# USB.net
KiCad netlist of a schematic drawn in Altium Designer
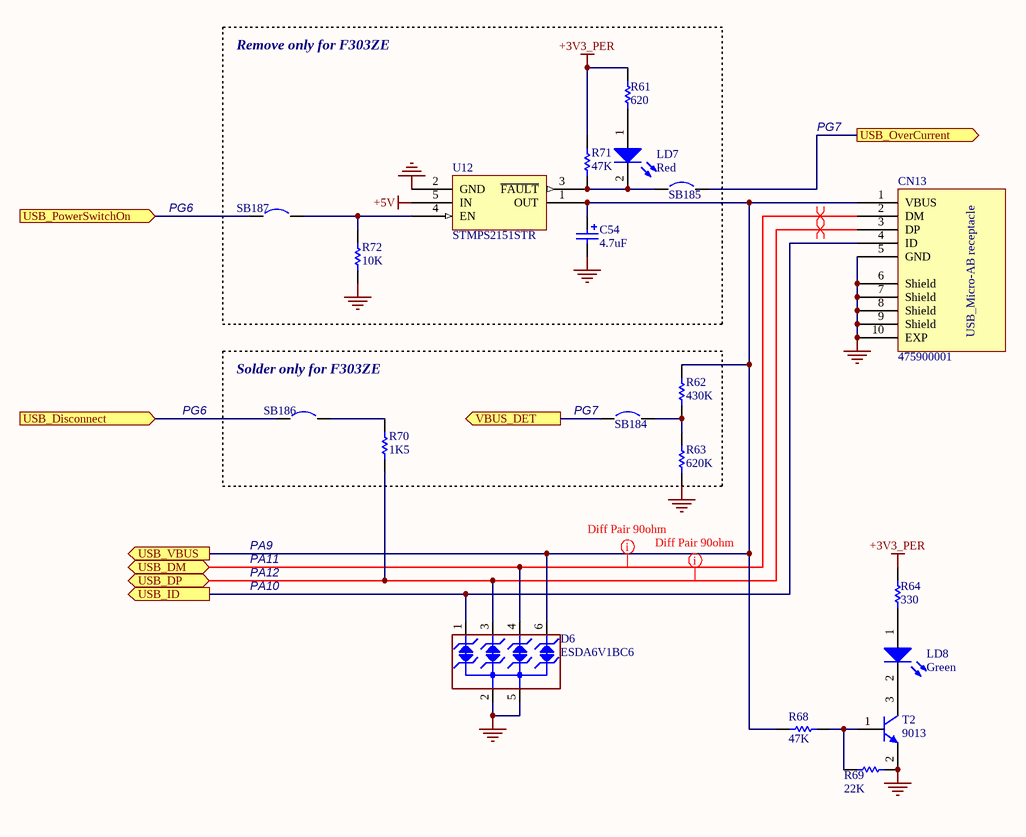
[diagram p0: USB.SchDoc]

(export (version "E")
  (design (tool "Eeschema 10.0.6"))
  (components
    (comp (ref "C54")
      (value "4.7uF")
      (footprint "TAN-A")
      (description "Polarized Capacitor (Radial)")
      (fields (field (name "PUBLISHER") "Altium Limited"))
      (libsource (lib "Miscellaneous Devices") (part "Cap Pol1"))
    )
    (comp (ref "CN13")
      (value "475900001")
      (footprint "MOLEX_47590001")
      (libsource (lib "mb1045") (part "475900001"))
    )
    (comp (ref "D6")
      (value "ESDA6V1BC6")
      (footprint "STM-SMEE:SOT23-6L")
      (description "4-line ESD protection")
      (libsource (lib "MB1137") (part "ESDA6V1BC6"))
    )
    (comp (ref "LD7")
      (value "Red")
      (footprint "0603D-R")
      (description "Typical RED, GREEN, YELLOW, AMBER GaAs LED")
      (fields (field (name "PUBLISHER") "Altium Limited"))
      (libsource (lib "Miscellaneous Devices") (part "LED2"))
    )
    (comp (ref "LD8")
      (value "Green")
      (footprint "0603D-G")
      (description "Typical RED, GREEN, YELLOW, AMBER GaAs LED")
      (fields (field (name "PUBLISHER") "Altium Limited"))
      (libsource (lib "Miscellaneous Devices") (part "LED2"))
    )
    (comp (ref "R61")
      (value "620")
      (footprint "0603R")
      (description "Resistor")
      (fields (field (name "PUBLISHER") "Altium Limited"))
      (libsource (lib "Miscellaneous Devices") (part "Res1"))
    )
    (comp (ref "R62")
      (value "430K")
      (footprint "0603R")
      (description "Resistor")
      (fields (field (name "PUBLISHER") "Altium Limited"))
      (libsource (lib "Miscellaneous Devices") (part "res1"))
    )
    (comp (ref "R63")
      (value "620K")
      (footprint "0603R")
      (description "Resistor")
      (fields (field (name "PUBLISHER") "Altium Limited"))
      (libsource (lib "Miscellaneous Devices") (part "res1"))
    )
    (comp (ref "R64")
      (value "330")
      (footprint "0603R")
      (description "Resistor")
      (fields (field (name "PUBLISHER") "Altium Limited"))
      (libsource (lib "Miscellaneous Devices") (part "res1"))
    )
    (comp (ref "R68")
      (value "47K")
      (footprint "0603R")
      (description "Resistor")
      (fields (field (name "PUBLISHER") "Altium Limited"))
      (libsource (lib "Miscellaneous Devices") (part "res1"))
    )
    (comp (ref "R69")
      (value "22K")
      (footprint "0603R")
      (description "Resistor")
      (fields (field (name "PUBLISHER") "Altium Limited"))
      (libsource (lib "Miscellaneous Devices") (part "res1"))
    )
    (comp (ref "R70")
      (value "1K5")
      (footprint "0603R")
      (description "Resistor 0402 / 0603 / 0805")
      (libsource (lib "") (part "Res1_1"))
    )
    (comp (ref "R71")
      (value "47K")
      (footprint "0603R")
      (description "Resistor")
      (fields (field (name "PUBLISHER") "Altium Limited"))
      (libsource (lib "Miscellaneous Devices") (part "res1"))
    )
    (comp (ref "R72")
      (value "10K")
      (footprint "0603R")
      (description "Resistor")
      (fields (field (name "PUBLISHER") "Altium Limited"))
      (libsource (lib "Miscellaneous Devices") (part "Res1"))
    )
    (comp (ref "SB184")
      (value "Circuit Breaker")
      (footprint "SB_0603")
      (fields (field (name "PUBLISHER") "Altium Limited"))
      (libsource (lib "MCD_TOOLS") (part "Circuit Breaker"))
    )
    (comp (ref "SB185")
      (value "Circuit Breaker")
      (footprint "SB_0603")
      (fields (field (name "PUBLISHER") "Altium Limited"))
      (libsource (lib "MCD_TOOLS") (part "Circuit Breaker"))
    )
    (comp (ref "SB186")
      (value "Circuit Breaker")
      (footprint "SB_0603")
      (fields (field (name "PUBLISHER") "Altium Limited"))
      (libsource (lib "MCD_TOOLS") (part "Circuit Breaker"))
    )
    (comp (ref "SB187")
      (value "Circuit Breaker")
      (footprint "SB_0603")
      (fields (field (name "PUBLISHER") "Altium Limited"))
      (libsource (lib "MCD_TOOLS") (part "Circuit Breaker"))
    )
    (comp (ref "T2")
      (value "9013")
      (footprint "SOT-23")
      (description "NPN Bipolar Transistor")
      (fields (field (name "PUBLISHER") "Altium Limited"))
      (libsource (lib "MB1167") (part "NPN"))
    )
    (comp (ref "U12")
      (value "STMPS2151STR")
      (footprint "SOT-23-5L")
      (libsource (lib "mb1045") (part "STMPS2141STR"))
    )
  )
  (nets
    (net (code "1") (name "+3V3_PER") (class "Default")
      (node (ref "R61") (pin "2") (pinfunction "2_2") (pintype "passive"))
      (node (ref "R64") (pin "2") (pinfunction "2_2") (pintype "passive"))
      (node (ref "R71") (pin "1") (pinfunction "1_1") (pintype "passive"))
    )
    (net (code "2") (name "+5V") (class "Default")
      (node (ref "U12") (pin "5") (pinfunction "IN_5") (pintype "passive"))
    )
    (net (code "3") (name "/USB_DM") (class "Default")
      (node (ref "CN13") (pin "2") (pinfunction "DM_2") (pintype "passive"))
      (node (ref "D6") (pin "4") (pinfunction "IO3_4") (pintype "passive"))
    )
    (net (code "4") (name "/USB_DP") (class "Default")
      (node (ref "CN13") (pin "3") (pinfunction "DP_3") (pintype "passive"))
      (node (ref "D6") (pin "3") (pinfunction "GND_3") (pintype "passive"))
      (node (ref "R70") (pin "1") (pinfunction "1_1") (pintype "passive"))
    )
    (net (code "5") (name "/USB_Disconnect") (class "Default")
      (node (ref "SB186") (pin "1") (pinfunction "1_1") (pintype "passive"))
    )
    (net (code "6") (name "/USB_ID") (class "Default")
      (node (ref "CN13") (pin "4") (pinfunction "ID_4") (pintype "passive"))
      (node (ref "D6") (pin "1") (pinfunction "IO1_1") (pintype "passive"))
    )
    (net (code "7") (name "/USB_OverCurrent") (class "Default")
      (node (ref "SB185") (pin "2") (pinfunction "2_2") (pintype "passive"))
    )
    (net (code "8") (name "/USB_PowerSwitchOn") (class "Default")
      (node (ref "SB187") (pin "1") (pinfunction "1_1") (pintype "passive"))
    )
    (net (code "9") (name "/USB_VBUS") (class "Default")
      (node (ref "C54") (pin "1") (pinfunction "1_1") (pintype "passive"))
      (node (ref "CN13") (pin "1") (pinfunction "VBUS_1") (pintype "passive"))
      (node (ref "D6") (pin "6") (pinfunction "NC_6") (pintype "passive"))
      (node (ref "R62") (pin "1") (pinfunction "1_1") (pintype "passive"))
      (node (ref "R68") (pin "1") (pinfunction "1_1") (pintype "passive"))
      (node (ref "U12") (pin "1") (pinfunction "OUT_1") (pintype "passive"))
    )
    (net (code "10") (name "/VBUS_DET") (class "Default")
      (node (ref "SB184") (pin "1") (pinfunction "1_1") (pintype "passive"))
    )
    (net (code "11") (name "GND") (class "Default")
      (node (ref "C54") (pin "2") (pinfunction "2_2") (pintype "passive"))
      (node (ref "CN13") (pin "10") (pinfunction "EXP_10") (pintype "passive"))
      (node (ref "CN13") (pin "5") (pinfunction "GND_5") (pintype "passive"))
      (node (ref "CN13") (pin "6") (pinfunction "Shield_6") (pintype "passive"))
      (node (ref "CN13") (pin "7") (pinfunction "Shield_7") (pintype "passive"))
      (node (ref "CN13") (pin "8") (pinfunction "Shield_8") (pintype "passive"))
      (node (ref "CN13") (pin "9") (pinfunction "Shield_9") (pintype "passive"))
      (node (ref "D6") (pin "2") (pinfunction "IO2_2") (pintype "passive"))
      (node (ref "D6") (pin "5") (pinfunction "IO4_5") (pintype "passive"))
      (node (ref "R63") (pin "2") (pinfunction "2_2") (pintype "passive"))
      (node (ref "R69") (pin "1") (pinfunction "1_1") (pintype "passive"))
      (node (ref "R72") (pin "1") (pinfunction "1_1") (pintype "passive"))
      (node (ref "T2") (pin "2") (pinfunction "E_2") (pintype "passive"))
      (node (ref "U12") (pin "2") (pinfunction "GND_2") (pintype "passive"))
    )
    (net (code "12") (name "Net-(LD7-A)") (class "Default")
      (node (ref "LD7") (pin "1") (pinfunction "A_1") (pintype "passive"))
      (node (ref "R61") (pin "1") (pinfunction "1_1") (pintype "passive"))
    )
    (net (code "13") (name "Net-(LD7-K)") (class "Default")
      (node (ref "LD7") (pin "2") (pinfunction "K_2") (pintype "passive"))
      (node (ref "R71") (pin "2") (pinfunction "2_2") (pintype "passive"))
      (node (ref "SB185") (pin "1") (pinfunction "1_1") (pintype "passive"))
      (node (ref "U12") (pin "3") (pinfunction "~{FAULT}_3") (pintype "output"))
    )
    (net (code "14") (name "Net-(LD8-A)") (class "Default")
      (node (ref "LD8") (pin "1") (pinfunction "A_1") (pintype "passive"))
      (node (ref "R64") (pin "1") (pinfunction "1_1") (pintype "passive"))
    )
    (net (code "15") (name "Net-(LD8-K)") (class "Default")
      (node (ref "LD8") (pin "2") (pinfunction "K_2") (pintype "passive"))
      (node (ref "T2") (pin "3") (pinfunction "C_3") (pintype "passive"))
    )
    (net (code "16") (name "Net-(R62-Pad2)") (class "Default")
      (node (ref "R62") (pin "2") (pinfunction "2_2") (pintype "passive"))
      (node (ref "R63") (pin "1") (pinfunction "1_1") (pintype "passive"))
      (node (ref "SB184") (pin "2") (pinfunction "2_2") (pintype "passive"))
    )
    (net (code "17") (name "Net-(R70-Pad2)") (class "Default")
      (node (ref "R70") (pin "2") (pinfunction "2_2") (pintype "passive"))
      (node (ref "SB186") (pin "2") (pinfunction "2_2") (pintype "passive"))
    )
    (net (code "18") (name "Net-(T2-B)") (class "Default")
      (node (ref "R68") (pin "2") (pinfunction "2_2") (pintype "passive"))
      (node (ref "R69") (pin "2") (pinfunction "2_2") (pintype "passive"))
      (node (ref "T2") (pin "1") (pinfunction "B_1") (pintype "passive"))
    )
    (net (code "19") (name "Net-(U12-EN)") (class "Default")
      (node (ref "R72") (pin "2") (pinfunction "2_2") (pintype "passive"))
      (node (ref "SB187") (pin "2") (pinfunction "2_2") (pintype "passive"))
      (node (ref "U12") (pin "4") (pinfunction "EN_4") (pintype "input"))
    )
  )
)
